# powerstage.net
KiCad netlist of a schematic drawn in EAGLE
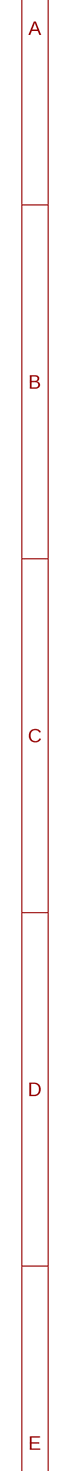
[diagram p0: schematic, sheet 1, part 1 of 2]
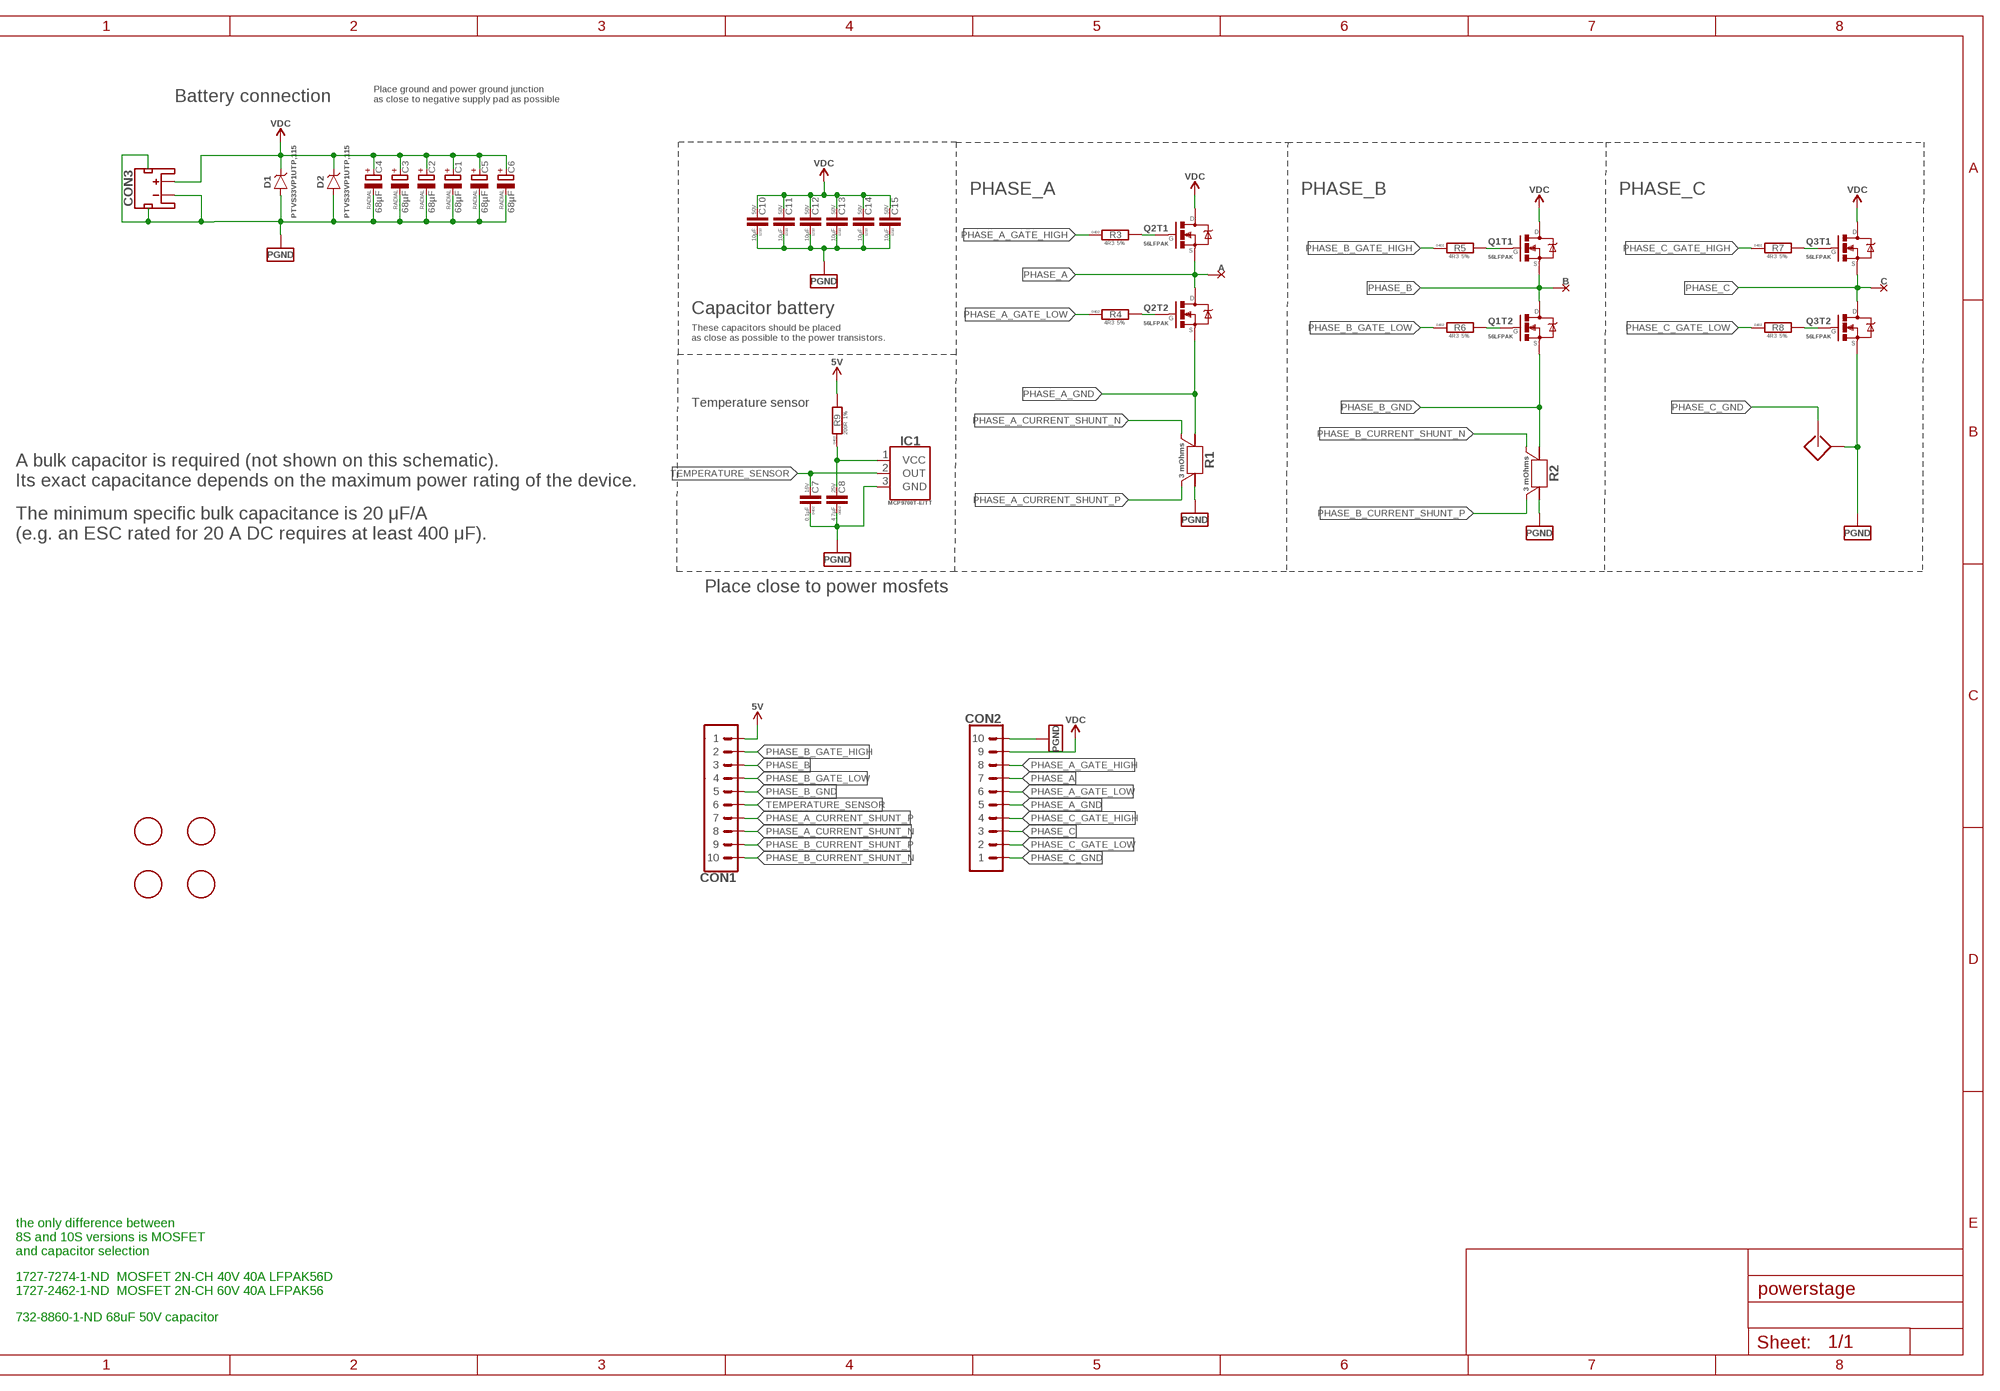
[diagram p1: schematic, sheet 1, part 2 of 2]

(export (version "E")
  (design (tool "Eeschema 10.0.6"))
  (components
    (comp (ref "A")
      (value "PAD-HOLE_2")
      (footprint "eagle-import:HOLE_2")
      (libsource (lib "eagle-import") (part "PAD-HOLE_2"))
    )
    (comp (ref "B")
      (value "PAD-HOLE_2")
      (footprint "eagle-import:HOLE_2")
      (libsource (lib "eagle-import") (part "PAD-HOLE_2"))
    )
    (comp (ref "C")
      (value "PAD-HOLE_2")
      (footprint "eagle-import:HOLE_2")
      (libsource (lib "eagle-import") (part "PAD-HOLE_2"))
    )
    (comp (ref "C1")
      (value "68µF")
      (footprint "eagle-import:RADIAL_6.3X12.5-RA")
      (fields
        (field (name "MANF") "Wurth Electronics Inc")
        (field (name "PACKAGE") "RADIAL")
        (field (name "TOLERANCE") "±20%")
        (field (name "VOLTAGE") "50V")
      )
      (libsource (lib "eagle-import") (part "CPOLRADIAL-6.3X12.5-RA-68UF_50V"))
    )
    (comp (ref "C2")
      (value "68µF")
      (footprint "eagle-import:RADIAL_6.3X12.5-RA")
      (fields
        (field (name "MANF") "Wurth Electronics Inc")
        (field (name "PACKAGE") "RADIAL")
        (field (name "TOLERANCE") "±20%")
        (field (name "VOLTAGE") "50V")
      )
      (libsource (lib "eagle-import") (part "CPOLRADIAL-6.3X12.5-RA-68UF_50V"))
    )
    (comp (ref "C3")
      (value "68µF")
      (footprint "eagle-import:RADIAL_6.3X12.5-RA")
      (fields
        (field (name "MANF") "Wurth Electronics Inc")
        (field (name "PACKAGE") "RADIAL")
        (field (name "TOLERANCE") "±20%")
        (field (name "VOLTAGE") "50V")
      )
      (libsource (lib "eagle-import") (part "CPOLRADIAL-6.3X12.5-RA-68UF_50V"))
    )
    (comp (ref "C4")
      (value "68µF")
      (footprint "eagle-import:RADIAL_6.3X12.5-RA")
      (fields
        (field (name "MANF") "Wurth Electronics Inc")
        (field (name "PACKAGE") "RADIAL")
        (field (name "TOLERANCE") "±20%")
        (field (name "VOLTAGE") "50V")
      )
      (libsource (lib "eagle-import") (part "CPOLRADIAL-6.3X12.5-RA-68UF_50V"))
    )
    (comp (ref "C5")
      (value "68µF")
      (footprint "eagle-import:RADIAL_6.3X12.5")
      (fields (field (name "PACKAGE") "RADIAL_6.3x12.5") (field (name "PACKAGE_1") "RADIAL"))
      (libsource (lib "eagle-import") (part "CPOL-RADIAL_6.3X12.5"))
    )
    (comp (ref "C6")
      (value "68µF")
      (footprint "eagle-import:RADIAL_6.3X12.5")
      (fields (field (name "PACKAGE") "RADIAL_6.3x12.5") (field (name "PACKAGE_1") "RADIAL"))
      (libsource (lib "eagle-import") (part "CPOL-RADIAL_6.3X12.5"))
    )
    (comp (ref "C7")
      (value "0.1µF")
      (footprint "eagle-import:C0402")
      (fields
        (field (name "MANF") "Murata Electronics North America")
        (field (name "PACKAGE") "0402")
        (field (name "TOLERANCE") "+-10%")
        (field (name "VOLTAGE") "16V")
      )
      (libsource (lib "eagle-import") (part "0.1µF-0402-16V_10%_X7R"))
    )
    (comp (ref "C8")
      (value "4.7µF")
      (footprint "eagle-import:C0603")
      (fields
        (field (name "MANF") "Murata Electronics North America")
        (field (name "PACKAGE") "0603")
        (field (name "TOLERANCE") "+-10%")
        (field (name "VOLTAGE") "25V")
      )
      (libsource (lib "eagle-import") (part "4.7µF-0603-25V_10%_X6S"))
    )
    (comp (ref "C10")
      (value "10µF")
      (footprint "eagle-import:C1210")
      (fields
        (field (name "MANF") "TDK Corporation")
        (field (name "PACKAGE") "1210")
        (field (name "TOLERANCE") "±10%")
        (field (name "VOLTAGE") "50V")
      )
      (libsource (lib "eagle-import") (part "10µF-C1210-50_10%_X7S"))
    )
    (comp (ref "C11")
      (value "10µF")
      (footprint "eagle-import:C1210")
      (fields
        (field (name "MANF") "TDK Corporation")
        (field (name "PACKAGE") "1210")
        (field (name "TOLERANCE") "±10%")
        (field (name "VOLTAGE") "50V")
      )
      (libsource (lib "eagle-import") (part "10µF-C1210-50_10%_X7S"))
    )
    (comp (ref "C12")
      (value "10µF")
      (footprint "eagle-import:C1210")
      (fields
        (field (name "MANF") "TDK Corporation")
        (field (name "PACKAGE") "1210")
        (field (name "TOLERANCE") "±10%")
        (field (name "VOLTAGE") "50V")
      )
      (libsource (lib "eagle-import") (part "10µF-C1210-50_10%_X7S"))
    )
    (comp (ref "C13")
      (value "10µF")
      (footprint "eagle-import:C1210")
      (fields
        (field (name "MANF") "TDK Corporation")
        (field (name "PACKAGE") "1210")
        (field (name "TOLERANCE") "±10%")
        (field (name "VOLTAGE") "50V")
      )
      (libsource (lib "eagle-import") (part "10µF-C1210-50_10%_X7S"))
    )
    (comp (ref "C14")
      (value "10µF")
      (footprint "eagle-import:C1210")
      (fields
        (field (name "MANF") "TDK Corporation")
        (field (name "PACKAGE") "1210")
        (field (name "TOLERANCE") "±10%")
        (field (name "VOLTAGE") "50V")
      )
      (libsource (lib "eagle-import") (part "10µF-C1210-50_10%_X7S"))
    )
    (comp (ref "C15")
      (value "10µF")
      (footprint "eagle-import:C1210")
      (fields
        (field (name "MANF") "TDK Corporation")
        (field (name "PACKAGE") "1210")
        (field (name "TOLERANCE") "±10%")
        (field (name "VOLTAGE") "50V")
      )
      (libsource (lib "eagle-import") (part "10µF-C1210-50_10%_X7S"))
    )
    (comp (ref "CON1")
      (value "PINHEAD_1X10-2-FEMALE")
      (footprint "eagle-import:1X10-PTH_2-FEMALE")
      (fields (field (name "MANF") "Sullins Connector Solutions"))
      (libsource (lib "eagle-import") (part "PINHEAD_1X10-2-FEMALE"))
    )
    (comp (ref "CON2")
      (value "PINHEAD_1X10-2-FEMALE")
      (footprint "eagle-import:1X10-PTH_2-FEMALE")
      (fields (field (name "MANF") "Sullins Connector Solutions"))
      (libsource (lib "eagle-import") (part "PINHEAD_1X10-2-FEMALE"))
    )
    (comp (ref "CON3")
      (value "BATTERY_CON-2P-XT30-RA")
      (footprint "eagle-import:XT30-RA")
      (fields (field (name "MANF") "AMASS"))
      (libsource (lib "eagle-import") (part "BATTERY_CON-2P-XT30-RA"))
    )
    (comp (ref "D1")
      (value "PTVS33VP1UTP,115-36V-SOD128")
      (footprint "eagle-import:SOD128")
      (fields (field (name "MANF") "Nexperia USA Inc") (field (name "MANF#") "PTVS33VP1UTP,115"))
      (libsource (lib "eagle-import") (part "PTVS33VP1UTP,115-SOD128-36V"))
    )
    (comp (ref "D2")
      (value "PTVS33VP1UTP,115-36V-SOD128")
      (footprint "eagle-import:SOD128")
      (fields (field (name "MANF") "Nexperia USA Inc") (field (name "MANF#") "PTVS33VP1UTP,115"))
      (libsource (lib "eagle-import") (part "PTVS33VP1UTP,115-SOD128-36V"))
    )
    (comp (ref "IC1")
      (value "MCP9700")
      (footprint "eagle-import:SOT23B-3")
      (fields (field (name "MANF#") "MCP9700T-E/TT") (field (name "MANF") "Microchip Technology"))
      (libsource (lib "eagle-import") (part "MCP9700"))
    )
    (comp (ref "Q1")
      (value "BUK9K6R2-40E,115")
      (footprint "eagle-import:SOT-1205")
      (fields (field (name "PACKAGE") "56LFPAK") (field (name "MANF") "NXP Semiconductors"))
      (libsource (lib "eagle-import") (part "BUK9K6R2-40E,115"))
    )
    (comp (ref "Q2")
      (value "BUK9K6R2-40E,115")
      (footprint "eagle-import:SOT-1205")
      (fields (field (name "PACKAGE") "56LFPAK") (field (name "MANF") "NXP Semiconductors"))
      (libsource (lib "eagle-import") (part "BUK9K6R2-40E,115"))
    )
    (comp (ref "Q3")
      (value "BUK9K6R2-40E,115")
      (footprint "eagle-import:SOT-1205")
      (fields (field (name "PACKAGE") "56LFPAK") (field (name "MANF") "NXP Semiconductors"))
      (libsource (lib "eagle-import") (part "BUK9K6R2-40E,115"))
    )
    (comp (ref "R1")
      (value "3 mOhms")
      (footprint "eagle-import:R2512-KELVIN")
      (fields
        (field (name "MANF") "Stackpole Electronics Inc.")
        (field (name "POWER") "2W")
        (field (name "TOLERANCE") "±1%")
      )
      (libsource (lib "eagle-import") (part "CURRENT_SHUNT_KELVIN-2512-KELVIN-0.003R"))
    )
    (comp (ref "R2")
      (value "3 mOhms")
      (footprint "eagle-import:R2512-KELVIN")
      (fields
        (field (name "MANF") "Stackpole Electronics Inc.")
        (field (name "POWER") "2W")
        (field (name "TOLERANCE") "±1%")
      )
      (libsource (lib "eagle-import") (part "CURRENT_SHUNT_KELVIN-2512-KELVIN-0.003R"))
    )
    (comp (ref "R3")
      (value "4R3")
      (footprint "eagle-import:R0402")
      (fields (field (name "MANF") "Yageo") (field (name "PACKAGE") "0402") (field (name "TOLERANCE") "5%"))
      (libsource (lib "eagle-import") (part "4R3-0402-5%"))
    )
    (comp (ref "R4")
      (value "4R3")
      (footprint "eagle-import:R0402")
      (fields (field (name "MANF") "Yageo") (field (name "PACKAGE") "0402") (field (name "TOLERANCE") "5%"))
      (libsource (lib "eagle-import") (part "4R3-0402-5%"))
    )
    (comp (ref "R5")
      (value "4R3")
      (footprint "eagle-import:R0402")
      (fields (field (name "MANF") "Yageo") (field (name "PACKAGE") "0402") (field (name "TOLERANCE") "5%"))
      (libsource (lib "eagle-import") (part "4R3-0402-5%"))
    )
    (comp (ref "R6")
      (value "4R3")
      (footprint "eagle-import:R0402")
      (fields (field (name "MANF") "Yageo") (field (name "PACKAGE") "0402") (field (name "TOLERANCE") "5%"))
      (libsource (lib "eagle-import") (part "4R3-0402-5%"))
    )
    (comp (ref "R7")
      (value "4R3")
      (footprint "eagle-import:R0402")
      (fields (field (name "MANF") "Yageo") (field (name "PACKAGE") "0402") (field (name "TOLERANCE") "5%"))
      (libsource (lib "eagle-import") (part "4R3-0402-5%"))
    )
    (comp (ref "R8")
      (value "4R3")
      (footprint "eagle-import:R0402")
      (fields (field (name "MANF") "Yageo") (field (name "PACKAGE") "0402") (field (name "TOLERANCE") "5%"))
      (libsource (lib "eagle-import") (part "4R3-0402-5%"))
    )
    (comp (ref "R9")
      (value "200R")
      (footprint "eagle-import:R0402")
      (fields (field (name "MANF") "Yageo") (field (name "PACKAGE") "0402") (field (name "TOLERANCE") "1%"))
      (libsource (lib "eagle-import") (part "200R-0402-1%"))
    )
    (comp (ref "S1")
      (value "SENSE")
      (footprint "eagle-import:SENSE-0.6")
      (libsource (lib "eagle-import") (part "SENSE"))
    )
    (comp (ref "U$8")
      (value "FIDUCIALMOUNT")
      (footprint "eagle-import:FIDUCIA-MOUNT")
      (libsource (lib "eagle-import") (part "FIDUCIALMOUNT"))
    )
    (comp (ref "U$9")
      (value "FIDUCIALMOUNT")
      (footprint "eagle-import:FIDUCIA-MOUNT")
      (libsource (lib "eagle-import") (part "FIDUCIALMOUNT"))
    )
    (comp (ref "U$10")
      (value "FIDUCIALMOUNT")
      (footprint "eagle-import:FIDUCIA-MOUNT")
      (libsource (lib "eagle-import") (part "FIDUCIALMOUNT"))
    )
    (comp (ref "U$12")
      (value "FIDUCIALMOUNT")
      (footprint "eagle-import:FIDUCIA-MOUNT")
      (libsource (lib "eagle-import") (part "FIDUCIALMOUNT"))
    )
  )
  (nets
    (net (code "1") (name "5V") (class "Default")
      (node (ref "CON1") (pin "1") (pinfunction "1_1") (pintype "passive"))
      (node (ref "R9") (pin "2") (pinfunction "2_2") (pintype "passive"))
    )
    (net (code "2") (name "Net-(C8-2)") (class "Default")
      (node (ref "C8") (pin "P$2") (pinfunction "2_P$2") (pintype "passive"))
      (node (ref "IC1") (pin "1") (pinfunction "VCC_1") (pintype "bidirectional"))
      (node (ref "R9") (pin "1") (pinfunction "1_1") (pintype "passive"))
    )
    (net (code "3") (name "Net-(Q1A-G)") (class "Default")
      (node (ref "Q1") (pin "2") (pinfunction "G_2") (pintype "passive"))
      (node (ref "R5") (pin "2") (pinfunction "2_2") (pintype "passive"))
    )
    (net (code "4") (name "Net-(Q1B-G)") (class "Default")
      (node (ref "Q1") (pin "4") (pinfunction "G_4") (pintype "passive"))
      (node (ref "R6") (pin "2") (pinfunction "2_2") (pintype "passive"))
    )
    (net (code "5") (name "Net-(Q2A-G)") (class "Default")
      (node (ref "Q2") (pin "2") (pinfunction "G_2") (pintype "passive"))
      (node (ref "R3") (pin "2") (pinfunction "2_2") (pintype "passive"))
    )
    (net (code "6") (name "Net-(Q2B-G)") (class "Default")
      (node (ref "Q2") (pin "4") (pinfunction "G_4") (pintype "passive"))
      (node (ref "R4") (pin "2") (pinfunction "2_2") (pintype "passive"))
    )
    (net (code "7") (name "Net-(Q3A-G)") (class "Default")
      (node (ref "Q3") (pin "2") (pinfunction "G_2") (pintype "passive"))
      (node (ref "R7") (pin "2") (pinfunction "2_2") (pintype "passive"))
    )
    (net (code "8") (name "Net-(Q3B-G)") (class "Default")
      (node (ref "Q3") (pin "4") (pinfunction "G_4") (pintype "passive"))
      (node (ref "R8") (pin "2") (pinfunction "2_2") (pintype "passive"))
    )
    (net (code "9") (name "PGND") (class "Default")
      (node (ref "C1") (pin "-") (pinfunction "-_-") (pintype "passive"))
      (node (ref "C10") (pin "1") (pinfunction "1_1") (pintype "passive"))
      (node (ref "C11") (pin "1") (pinfunction "1_1") (pintype "passive"))
      (node (ref "C12") (pin "1") (pinfunction "1_1") (pintype "passive"))
      (node (ref "C13") (pin "1") (pinfunction "1_1") (pintype "passive"))
      (node (ref "C14") (pin "1") (pinfunction "1_1") (pintype "passive"))
      (node (ref "C15") (pin "1") (pinfunction "1_1") (pintype "passive"))
      (node (ref "C2") (pin "-") (pinfunction "-_-") (pintype "passive"))
      (node (ref "C3") (pin "-") (pinfunction "-_-") (pintype "passive"))
      (node (ref "C4") (pin "-") (pinfunction "-_-") (pintype "passive"))
      (node (ref "C5") (pin "-") (pinfunction "-_-") (pintype "passive"))
      (node (ref "C6") (pin "-") (pinfunction "-_-") (pintype "passive"))
      (node (ref "C7") (pin "1") (pinfunction "1_1") (pintype "passive"))
      (node (ref "C8") (pin "P$1") (pinfunction "1_P$1") (pintype "passive"))
      (node (ref "CON2") (pin "10") (pinfunction "10_10") (pintype "passive"))
      (node (ref "CON3") (pin "-") (pinfunction "-_-") (pintype "bidirectional"))
      (node (ref "CON3") (pin "P$3") (pinfunction "PAD1_P$3") (pintype "bidirectional"))
      (node (ref "CON3") (pin "P$4") (pinfunction "PAD2_P$4") (pintype "bidirectional"))
      (node (ref "D1") (pin "A") (pinfunction "A_A") (pintype "passive"))
      (node (ref "D2") (pin "A") (pinfunction "A_A") (pintype "passive"))
      (node (ref "IC1") (pin "3") (pinfunction "GND_3") (pintype "bidirectional"))
      (node (ref "Q3") (pin "3") (pinfunction "S_3") (pintype "passive"))
      (node (ref "R1") (pin "2") (pinfunction "2_2") (pintype "bidirectional"))
      (node (ref "R1") (pin "22") (pinfunction "2_22") (pintype "bidirectional"))
      (node (ref "R2") (pin "2") (pinfunction "2_2") (pintype "bidirectional"))
      (node (ref "R2") (pin "22") (pinfunction "2_22") (pintype "bidirectional"))
      (node (ref "S1") (pin "SHELL") (pinfunction "SHELLL_SHELL") (pintype "bidirectional"))
    )
    (net (code "10") (name "PHASE_A") (class "Default")
      (node (ref "A") (pin "P$1") (pinfunction "P$1_P$1") (pintype "bidirectional"))
      (node (ref "CON2") (pin "7") (pinfunction "7_7") (pintype "passive"))
      (node (ref "Q2") (pin "1") (pinfunction "S_1") (pintype "passive"))
      (node (ref "Q2") (pin "5") (pinfunction "D_5") (pintype "passive"))
      (node (ref "Q2") (pin "6") (pinfunction "D_6") (pintype "passive"))
      (node (ref "Q2") (pin "EP-5-6") (pinfunction "D_EP-5-6") (pintype "passive"))
    )
    (net (code "11") (name "PHASE_A_CURRENT_SHUNT_N") (class "Default")
      (node (ref "CON1") (pin "8") (pinfunction "8_8") (pintype "passive"))
      (node (ref "R1") (pin "S1") (pinfunction "S1_S1") (pintype "bidirectional"))
    )
    (net (code "12") (name "PHASE_A_CURRENT_SHUNT_P") (class "Default")
      (node (ref "CON1") (pin "7") (pinfunction "7_7") (pintype "passive"))
      (node (ref "R1") (pin "S2") (pinfunction "S2_S2") (pintype "bidirectional"))
    )
    (net (code "13") (name "PHASE_A_GATE_HIGH") (class "Default")
      (node (ref "CON2") (pin "8") (pinfunction "8_8") (pintype "passive"))
      (node (ref "R3") (pin "1") (pinfunction "1_1") (pintype "passive"))
    )
    (net (code "14") (name "PHASE_A_GATE_LOW") (class "Default")
      (node (ref "CON2") (pin "6") (pinfunction "6_6") (pintype "passive"))
      (node (ref "R4") (pin "1") (pinfunction "1_1") (pintype "passive"))
    )
    (net (code "15") (name "PHASE_A_GND") (class "Default")
      (node (ref "CON2") (pin "5") (pinfunction "5_5") (pintype "passive"))
      (node (ref "Q2") (pin "3") (pinfunction "S_3") (pintype "passive"))
      (node (ref "R1") (pin "1") (pinfunction "1_1") (pintype "bidirectional"))
      (node (ref "R1") (pin "11") (pinfunction "1_11") (pintype "bidirectional"))
    )
    (net (code "16") (name "PHASE_B") (class "Default")
      (node (ref "B") (pin "P$1") (pinfunction "P$1_P$1") (pintype "bidirectional"))
      (node (ref "CON1") (pin "3") (pinfunction "3_3") (pintype "passive"))
      (node (ref "Q1") (pin "1") (pinfunction "S_1") (pintype "passive"))
      (node (ref "Q1") (pin "5") (pinfunction "D_5") (pintype "passive"))
      (node (ref "Q1") (pin "6") (pinfunction "D_6") (pintype "passive"))
      (node (ref "Q1") (pin "EP-5-6") (pinfunction "D_EP-5-6") (pintype "passive"))
    )
    (net (code "17") (name "PHASE_B_CURRENT_SHUNT_N") (class "Default")
      (node (ref "CON1") (pin "10") (pinfunction "10_10") (pintype "passive"))
      (node (ref "R2") (pin "S1") (pinfunction "S1_S1") (pintype "bidirectional"))
    )
    (net (code "18") (name "PHASE_B_CURRENT_SHUNT_P") (class "Default")
      (node (ref "CON1") (pin "9") (pinfunction "9_9") (pintype "passive"))
      (node (ref "R2") (pin "S2") (pinfunction "S2_S2") (pintype "bidirectional"))
    )
    (net (code "19") (name "PHASE_B_GATE_HIGH") (class "Default")
      (node (ref "CON1") (pin "2") (pinfunction "2_2") (pintype "passive"))
      (node (ref "R5") (pin "1") (pinfunction "1_1") (pintype "passive"))
    )
    (net (code "20") (name "PHASE_B_GATE_LOW") (class "Default")
      (node (ref "CON1") (pin "4") (pinfunction "4_4") (pintype "passive"))
      (node (ref "R6") (pin "1") (pinfunction "1_1") (pintype "passive"))
    )
    (net (code "21") (name "PHASE_B_GND") (class "Default")
      (node (ref "CON1") (pin "5") (pinfunction "5_5") (pintype "passive"))
      (node (ref "Q1") (pin "3") (pinfunction "S_3") (pintype "passive"))
      (node (ref "R2") (pin "1") (pinfunction "1_1") (pintype "bidirectional"))
      (node (ref "R2") (pin "11") (pinfunction "1_11") (pintype "bidirectional"))
    )
    (net (code "22") (name "PHASE_C") (class "Default")
      (node (ref "C") (pin "P$1") (pinfunction "P$1_P$1") (pintype "bidirectional"))
      (node (ref "CON2") (pin "3") (pinfunction "3_3") (pintype "passive"))
      (node (ref "Q3") (pin "1") (pinfunction "S_1") (pintype "passive"))
      (node (ref "Q3") (pin "5") (pinfunction "D_5") (pintype "passive"))
      (node (ref "Q3") (pin "6") (pinfunction "D_6") (pintype "passive"))
      (node (ref "Q3") (pin "EP-5-6") (pinfunction "D_EP-5-6") (pintype "passive"))
    )
    (net (code "23") (name "PHASE_C_GATE_HIGH") (class "Default")
      (node (ref "CON2") (pin "4") (pinfunction "4_4") (pintype "passive"))
      (node (ref "R7") (pin "1") (pinfunction "1_1") (pintype "passive"))
    )
    (net (code "24") (name "PHASE_C_GATE_LOW") (class "Default")
      (node (ref "CON2") (pin "2") (pinfunction "2_2") (pintype "passive"))
      (node (ref "R8") (pin "1") (pinfunction "1_1") (pintype "passive"))
    )
    (net (code "25") (name "PHASE_C_GND") (class "Default")
      (node (ref "CON2") (pin "1") (pinfunction "1_1") (pintype "passive"))
      (node (ref "S1") (pin "IN") (pinfunction "IN_IN") (pintype "bidirectional"))
    )
    (net (code "26") (name "TEMPERATURE_SENSOR") (class "Default")
      (node (ref "C7") (pin "2") (pinfunction "2_2") (pintype "passive"))
      (node (ref "CON1") (pin "6") (pinfunction "6_6") (pintype "passive"))
      (node (ref "IC1") (pin "2") (pinfunction "OUT_2") (pintype "bidirectional"))
    )
    (net (code "27") (name "VDC") (class "Default")
      (node (ref "C1") (pin "+") (pinfunction "+_+") (pintype "passive"))
      (node (ref "C10") (pin "2") (pinfunction "2_2") (pintype "passive"))
      (node (ref "C11") (pin "2") (pinfunction "2_2") (pintype "passive"))
      (node (ref "C12") (pin "2") (pinfunction "2_2") (pintype "passive"))
      (node (ref "C13") (pin "2") (pinfunction "2_2") (pintype "passive"))
      (node (ref "C14") (pin "2") (pinfunction "2_2") (pintype "passive"))
      (node (ref "C15") (pin "2") (pinfunction "2_2") (pintype "passive"))
      (node (ref "C2") (pin "+") (pinfunction "+_+") (pintype "passive"))
      (node (ref "C3") (pin "+") (pinfunction "+_+") (pintype "passive"))
      (node (ref "C4") (pin "+") (pinfunction "+_+") (pintype "passive"))
      (node (ref "C5") (pin "+") (pinfunction "+_+") (pintype "passive"))
      (node (ref "C6") (pin "+") (pinfunction "+_+") (pintype "passive"))
      (node (ref "CON2") (pin "9") (pinfunction "9_9") (pintype "passive"))
      (node (ref "CON3") (pin "+") (pinfunction "+_+") (pintype "bidirectional"))
      (node (ref "D1") (pin "C") (pinfunction "C_C") (pintype "passive"))
      (node (ref "D2") (pin "C") (pinfunction "C_C") (pintype "passive"))
      (node (ref "Q1") (pin "7") (pinfunction "D_7") (pintype "passive"))
      (node (ref "Q1") (pin "8") (pinfunction "D_8") (pintype "passive"))
      (node (ref "Q1") (pin "EP-7-8") (pinfunction "D_EP-7-8") (pintype "passive"))
      (node (ref "Q2") (pin "7") (pinfunction "D_7") (pintype "passive"))
      (node (ref "Q2") (pin "8") (pinfunction "D_8") (pintype "passive"))
      (node (ref "Q2") (pin "EP-7-8") (pinfunction "D_EP-7-8") (pintype "passive"))
      (node (ref "Q3") (pin "7") (pinfunction "D_7") (pintype "passive"))
      (node (ref "Q3") (pin "8") (pinfunction "D_8") (pintype "passive"))
      (node (ref "Q3") (pin "EP-7-8") (pinfunction "D_EP-7-8") (pintype "passive"))
    )
  )
)
